# 14DoF.net
KiCad netlist of a schematic drawn in EAGLE
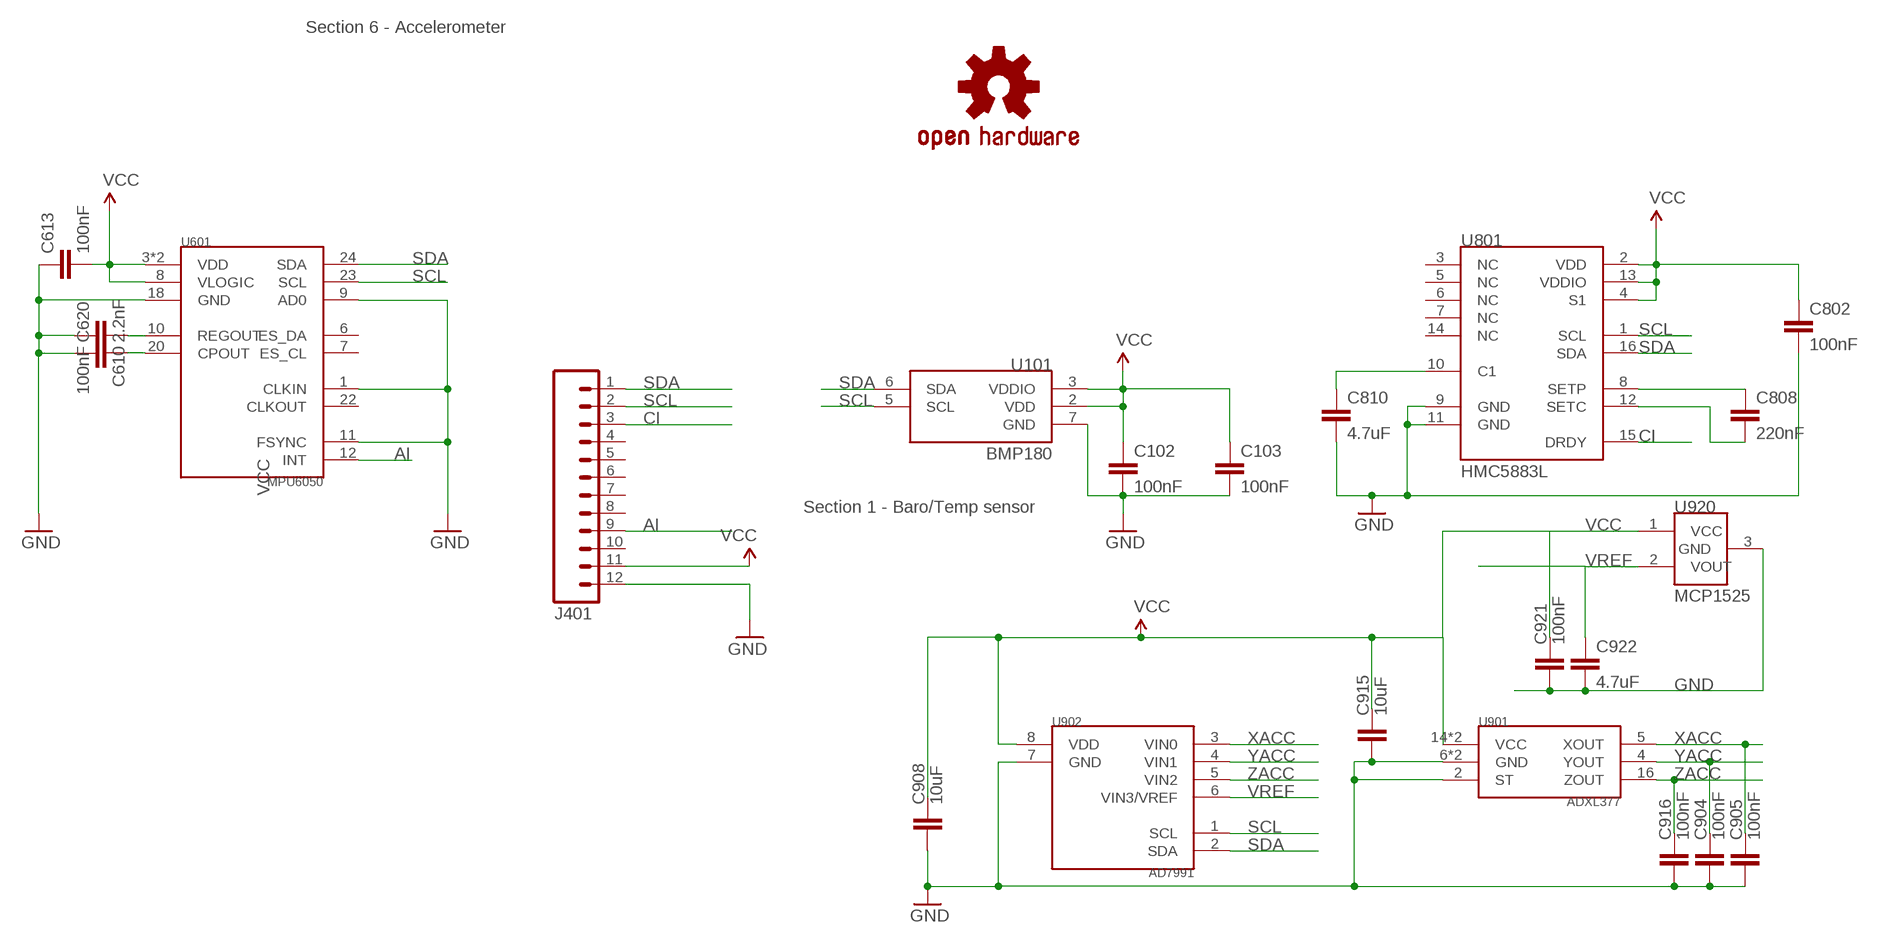
[diagram p0: schematic, sheet 1]

(export (version "E")
  (design (tool "Eeschema 10.0.6"))
  (components
    (comp (ref "C102")
      (value "100nF")
      (footprint "eagle-import:0603-CAP")
      (libsource (lib "eagle-import") (part "CAP0603-CAP"))
    )
    (comp (ref "C103")
      (value "100nF")
      (footprint "eagle-import:0603-CAP")
      (libsource (lib "eagle-import") (part "CAP0603-CAP"))
    )
    (comp (ref "C610")
      (value "100nF")
      (footprint "eagle-import:0603-CAP")
      (libsource (lib "eagle-import") (part "CAP0603-CAP"))
    )
    (comp (ref "C613")
      (value "100nF")
      (footprint "eagle-import:0603-CAP")
      (libsource (lib "eagle-import") (part "CAP0603-CAP"))
    )
    (comp (ref "C620")
      (value "2.2nF")
      (footprint "eagle-import:0603-CAP")
      (libsource (lib "eagle-import") (part "CAP0603-CAP"))
    )
    (comp (ref "C802")
      (value "100nF")
      (footprint "eagle-import:0603-CAP")
      (libsource (lib "eagle-import") (part "CAP0603-CAP"))
    )
    (comp (ref "C808")
      (value "220nF")
      (footprint "eagle-import:0603-CAP")
      (libsource (lib "eagle-import") (part "CAP0603-CAP"))
    )
    (comp (ref "C810")
      (value "4.7uF")
      (footprint "eagle-import:0603-CAP")
      (libsource (lib "eagle-import") (part "CAP0603-CAP"))
    )
    (comp (ref "C904")
      (value "100nF")
      (footprint "eagle-import:0603-CAP")
      (libsource (lib "eagle-import") (part "CAP0603-CAP"))
    )
    (comp (ref "C905")
      (value "100nF")
      (footprint "eagle-import:0603-CAP")
      (libsource (lib "eagle-import") (part "CAP0603-CAP"))
    )
    (comp (ref "C908")
      (value "10uF")
      (footprint "eagle-import:0603-CAP")
      (libsource (lib "eagle-import") (part "CAP0603-CAP"))
    )
    (comp (ref "C915")
      (value "10uF")
      (footprint "eagle-import:0603-CAP")
      (libsource (lib "eagle-import") (part "CAP0603-CAP"))
    )
    (comp (ref "C916")
      (value "100nF")
      (footprint "eagle-import:0603-CAP")
      (libsource (lib "eagle-import") (part "CAP0603-CAP"))
    )
    (comp (ref "C921")
      (value "100nF")
      (footprint "eagle-import:0603-CAP")
      (libsource (lib "eagle-import") (part "SparkFun-Passives_CAP0603-CAP"))
    )
    (comp (ref "C922")
      (value "4.7uF")
      (footprint "eagle-import:0603-CAP")
      (libsource (lib "eagle-import") (part "SparkFun-Passives_CAP0603-CAP"))
    )
    (comp (ref "J401")
      (value "M12PTH")
      (footprint "eagle-import:1X12")
      (libsource (lib "eagle-import") (part "M12PTH"))
    )
    (comp (ref "U$2")
      (value "OSHW-LOGOS")
      (footprint "eagle-import:OSHW-LOGO-S")
      (libsource (lib "eagle-import") (part "OSHW-LOGOS"))
    )
    (comp (ref "U101")
      (value "BMP180")
      (footprint "eagle-import:BMP180")
      (libsource (lib "eagle-import") (part "BMP180"))
    )
    (comp (ref "U601")
      (value "MPU6050")
      (footprint "eagle-import:MPU60X0")
      (libsource (lib "eagle-import") (part "MPU6050"))
    )
    (comp (ref "U801")
      (value "HMC5883L")
      (footprint "eagle-import:16LPCC")
      (libsource (lib "eagle-import") (part "HMC5883LSMD"))
    )
    (comp (ref "U901")
      (value "ADXL377")
      (footprint "eagle-import:ADXL377")
      (libsource (lib "eagle-import") (part "ADXL377"))
    )
    (comp (ref "U902")
      (value "AD7991")
      (footprint "eagle-import:SOT-23-8")
      (libsource (lib "eagle-import") (part "AD799X"))
    )
    (comp (ref "U920")
      (value "MCP1525")
      (footprint "eagle-import:SOT-23-3")
      (libsource (lib "eagle-import") (part "MCP1525"))
    )
  )
  (nets
    (net (code "1") (name "/AI") (class "Default")
      (node (ref "J401") (pin "9") (pinfunction "9_9") (pintype "passive"))
      (node (ref "U601") (pin "12") (pinfunction "INT_12") (pintype "bidirectional"))
    )
    (net (code "2") (name "/CI") (class "Default")
      (node (ref "J401") (pin "3") (pinfunction "3_3") (pintype "passive"))
      (node (ref "U801") (pin "15") (pinfunction "DRDY_15") (pintype "bidirectional"))
    )
    (net (code "3") (name "/SCL") (class "Default")
      (node (ref "J401") (pin "2") (pinfunction "2_2") (pintype "passive"))
      (node (ref "U101") (pin "5") (pinfunction "SCL_5") (pintype "input"))
      (node (ref "U601") (pin "23") (pinfunction "SCL_23") (pintype "bidirectional"))
      (node (ref "U801") (pin "1") (pinfunction "SCL_1") (pintype "bidirectional"))
      (node (ref "U902") (pin "1") (pinfunction "SCL_1") (pintype "bidirectional"))
    )
    (net (code "4") (name "/SDA") (class "Default")
      (node (ref "J401") (pin "1") (pinfunction "1_1") (pintype "passive"))
      (node (ref "U101") (pin "6") (pinfunction "SDA_6") (pintype "bidirectional"))
      (node (ref "U601") (pin "24") (pinfunction "SDA_24") (pintype "bidirectional"))
      (node (ref "U801") (pin "16") (pinfunction "SDA_16") (pintype "bidirectional"))
      (node (ref "U902") (pin "2") (pinfunction "SDA_2") (pintype "bidirectional"))
    )
    (net (code "5") (name "/VREF") (class "Default")
      (node (ref "C922") (pin "1") (pinfunction "1_1") (pintype "passive"))
      (node (ref "U902") (pin "6") (pinfunction "VIN3/VREF_6") (pintype "bidirectional"))
      (node (ref "U920") (pin "2") (pinfunction "VOUT_2") (pintype "bidirectional"))
    )
    (net (code "6") (name "/XACC") (class "Default")
      (node (ref "C905") (pin "1") (pinfunction "1_1") (pintype "passive"))
      (node (ref "U901") (pin "5") (pinfunction "XOUT_5") (pintype "bidirectional"))
      (node (ref "U902") (pin "3") (pinfunction "VIN0_3") (pintype "bidirectional"))
    )
    (net (code "7") (name "/YACC") (class "Default")
      (node (ref "C904") (pin "1") (pinfunction "1_1") (pintype "passive"))
      (node (ref "U901") (pin "4") (pinfunction "YOUT_4") (pintype "bidirectional"))
      (node (ref "U902") (pin "4") (pinfunction "VIN1_4") (pintype "bidirectional"))
    )
    (net (code "8") (name "/ZACC") (class "Default")
      (node (ref "C916") (pin "1") (pinfunction "1_1") (pintype "passive"))
      (node (ref "U901") (pin "16") (pinfunction "ZOUT_16") (pintype "bidirectional"))
      (node (ref "U902") (pin "5") (pinfunction "VIN2_5") (pintype "bidirectional"))
    )
    (net (code "9") (name "GND") (class "Default")
      (node (ref "C102") (pin "2") (pinfunction "2_2") (pintype "passive"))
      (node (ref "C103") (pin "2") (pinfunction "2_2") (pintype "passive"))
      (node (ref "C610") (pin "2") (pinfunction "2_2") (pintype "passive"))
      (node (ref "C613") (pin "1") (pinfunction "1_1") (pintype "passive"))
      (node (ref "C620") (pin "1") (pinfunction "1_1") (pintype "passive"))
      (node (ref "C802") (pin "2") (pinfunction "2_2") (pintype "passive"))
      (node (ref "C810") (pin "2") (pinfunction "2_2") (pintype "passive"))
      (node (ref "C904") (pin "2") (pinfunction "2_2") (pintype "passive"))
      (node (ref "C905") (pin "2") (pinfunction "2_2") (pintype "passive"))
      (node (ref "C908") (pin "2") (pinfunction "2_2") (pintype "passive"))
      (node (ref "C915") (pin "2") (pinfunction "2_2") (pintype "passive"))
      (node (ref "C916") (pin "2") (pinfunction "2_2") (pintype "passive"))
      (node (ref "C921") (pin "2") (pinfunction "2_2") (pintype "passive"))
      (node (ref "C922") (pin "2") (pinfunction "2_2") (pintype "passive"))
      (node (ref "J401") (pin "12") (pinfunction "12_12") (pintype "passive"))
      (node (ref "U101") (pin "7") (pinfunction "GND_7") (pintype "power_in"))
      (node (ref "U601") (pin "1") (pinfunction "CLKIN_1") (pintype "bidirectional"))
      (node (ref "U601") (pin "11") (pinfunction "FSYNC_11") (pintype "bidirectional"))
      (node (ref "U601") (pin "18") (pinfunction "GND_18") (pintype "bidirectional"))
      (node (ref "U601") (pin "9") (pinfunction "AD0_9") (pintype "bidirectional"))
      (node (ref "U801") (pin "11") (pinfunction "GND_11") (pintype "bidirectional"))
      (node (ref "U801") (pin "9") (pinfunction "GND_9") (pintype "bidirectional"))
      (node (ref "U901") (pin "2") (pinfunction "ST_2") (pintype "bidirectional"))
      (node (ref "U901") (pin "6") (pinfunction "GND_6") (pintype "bidirectional"))
      (node (ref "U901") (pin "7") (pinfunction "GND_7") (pintype "bidirectional"))
      (node (ref "U902") (pin "7") (pinfunction "GND_7") (pintype "bidirectional"))
      (node (ref "U920") (pin "3") (pinfunction "GND_3") (pintype "bidirectional"))
    )
    (net (code "10") (name "Net-(U601-CPOUT)") (class "Default")
      (node (ref "C620") (pin "2") (pinfunction "2_2") (pintype "passive"))
      (node (ref "U601") (pin "20") (pinfunction "CPOUT_20") (pintype "bidirectional"))
    )
    (net (code "11") (name "Net-(U601-REGOUT)") (class "Default")
      (node (ref "C610") (pin "1") (pinfunction "1_1") (pintype "passive"))
      (node (ref "U601") (pin "10") (pinfunction "REGOUT_10") (pintype "bidirectional"))
    )
    (net (code "12") (name "Net-(U801-C1)") (class "Default")
      (node (ref "C810") (pin "1") (pinfunction "1_1") (pintype "passive"))
      (node (ref "U801") (pin "10") (pinfunction "C1_10") (pintype "bidirectional"))
    )
    (net (code "13") (name "Net-(U801-SETC)") (class "Default")
      (node (ref "C808") (pin "2") (pinfunction "2_2") (pintype "passive"))
      (node (ref "U801") (pin "12") (pinfunction "SETC_12") (pintype "bidirectional"))
    )
    (net (code "14") (name "Net-(U801-SETP)") (class "Default")
      (node (ref "C808") (pin "1") (pinfunction "1_1") (pintype "passive"))
      (node (ref "U801") (pin "8") (pinfunction "SETP_8") (pintype "bidirectional"))
    )
    (net (code "15") (name "VCC") (class "Default")
      (node (ref "C102") (pin "1") (pinfunction "1_1") (pintype "passive"))
      (node (ref "C103") (pin "1") (pinfunction "1_1") (pintype "passive"))
      (node (ref "C613") (pin "2") (pinfunction "2_2") (pintype "passive"))
      (node (ref "C802") (pin "1") (pinfunction "1_1") (pintype "passive"))
      (node (ref "C908") (pin "1") (pinfunction "1_1") (pintype "passive"))
      (node (ref "C915") (pin "1") (pinfunction "1_1") (pintype "passive"))
      (node (ref "C921") (pin "1") (pinfunction "1_1") (pintype "passive"))
      (node (ref "J401") (pin "11") (pinfunction "11_11") (pintype "passive"))
      (node (ref "U101") (pin "2") (pinfunction "VDD_2") (pintype "power_in"))
      (node (ref "U101") (pin "3") (pinfunction "VDDIO_3") (pintype "power_in"))
      (node (ref "U601") (pin "13") (pinfunction "VDD_13") (pintype "bidirectional"))
      (node (ref "U601") (pin "3") (pinfunction "VDD_3") (pintype "bidirectional"))
      (node (ref "U601") (pin "8") (pinfunction "VLOGIC_8") (pintype "bidirectional"))
      (node (ref "U801") (pin "13") (pinfunction "VDDIO_13") (pintype "bidirectional"))
      (node (ref "U801") (pin "2") (pinfunction "VDD_2") (pintype "bidirectional"))
      (node (ref "U801") (pin "4") (pinfunction "S1_4") (pintype "bidirectional"))
      (node (ref "U901") (pin "14") (pinfunction "VCC_14") (pintype "bidirectional"))
      (node (ref "U901") (pin "15") (pinfunction "VCC_15") (pintype "bidirectional"))
      (node (ref "U902") (pin "8") (pinfunction "VDD_8") (pintype "bidirectional"))
      (node (ref "U920") (pin "1") (pinfunction "VCC_1") (pintype "bidirectional"))
    )
    (net (code "16") (name "unconnected-(J401-Pad4)") (class "Default")
      (node (ref "J401") (pin "4") (pinfunction "4_4") (pintype "passive"))
    )
    (net (code "17") (name "unconnected-(J401-Pad5)") (class "Default")
      (node (ref "J401") (pin "5") (pinfunction "5_5") (pintype "passive"))
    )
    (net (code "18") (name "unconnected-(J401-Pad6)") (class "Default")
      (node (ref "J401") (pin "6") (pinfunction "6_6") (pintype "passive"))
    )
    (net (code "19") (name "unconnected-(J401-Pad7)") (class "Default")
      (node (ref "J401") (pin "7") (pinfunction "7_7") (pintype "passive"))
    )
    (net (code "20") (name "unconnected-(J401-Pad8)") (class "Default")
      (node (ref "J401") (pin "8") (pinfunction "8_8") (pintype "passive"))
    )
    (net (code "21") (name "unconnected-(J401-Pad10)") (class "Default")
      (node (ref "J401") (pin "10") (pinfunction "10_10") (pintype "passive"))
    )
    (net (code "22") (name "unconnected-(U601-CLKOUT-Pad22)") (class "Default")
      (node (ref "U601") (pin "22") (pinfunction "CLKOUT_22") (pintype "bidirectional"))
    )
    (net (code "23") (name "unconnected-(U601-ES_CL-Pad7)") (class "Default")
      (node (ref "U601") (pin "7") (pinfunction "ES_CL_7") (pintype "bidirectional"))
    )
    (net (code "24") (name "unconnected-(U601-ES_DA-Pad6)") (class "Default")
      (node (ref "U601") (pin "6") (pinfunction "ES_DA_6") (pintype "bidirectional"))
    )
    (net (code "25") (name "unconnected-(U801-NC-Pad3)") (class "Default")
      (node (ref "U801") (pin "3") (pinfunction "NC_3") (pintype "bidirectional"))
    )
    (net (code "26") (name "unconnected-(U801-NC-Pad5)") (class "Default")
      (node (ref "U801") (pin "5") (pinfunction "NC_5") (pintype "bidirectional"))
    )
    (net (code "27") (name "unconnected-(U801-NC-Pad6)") (class "Default")
      (node (ref "U801") (pin "6") (pinfunction "NC_6") (pintype "bidirectional"))
    )
    (net (code "28") (name "unconnected-(U801-NC-Pad7)") (class "Default")
      (node (ref "U801") (pin "7") (pinfunction "NC_7") (pintype "bidirectional"))
    )
    (net (code "29") (name "unconnected-(U801-NC-Pad14)") (class "Default")
      (node (ref "U801") (pin "14") (pinfunction "NC_14") (pintype "bidirectional"))
    )
  )
)
